# Heart-Earrings_2025-02-13.net
KiCad netlist of a schematic drawn in Altium Designer
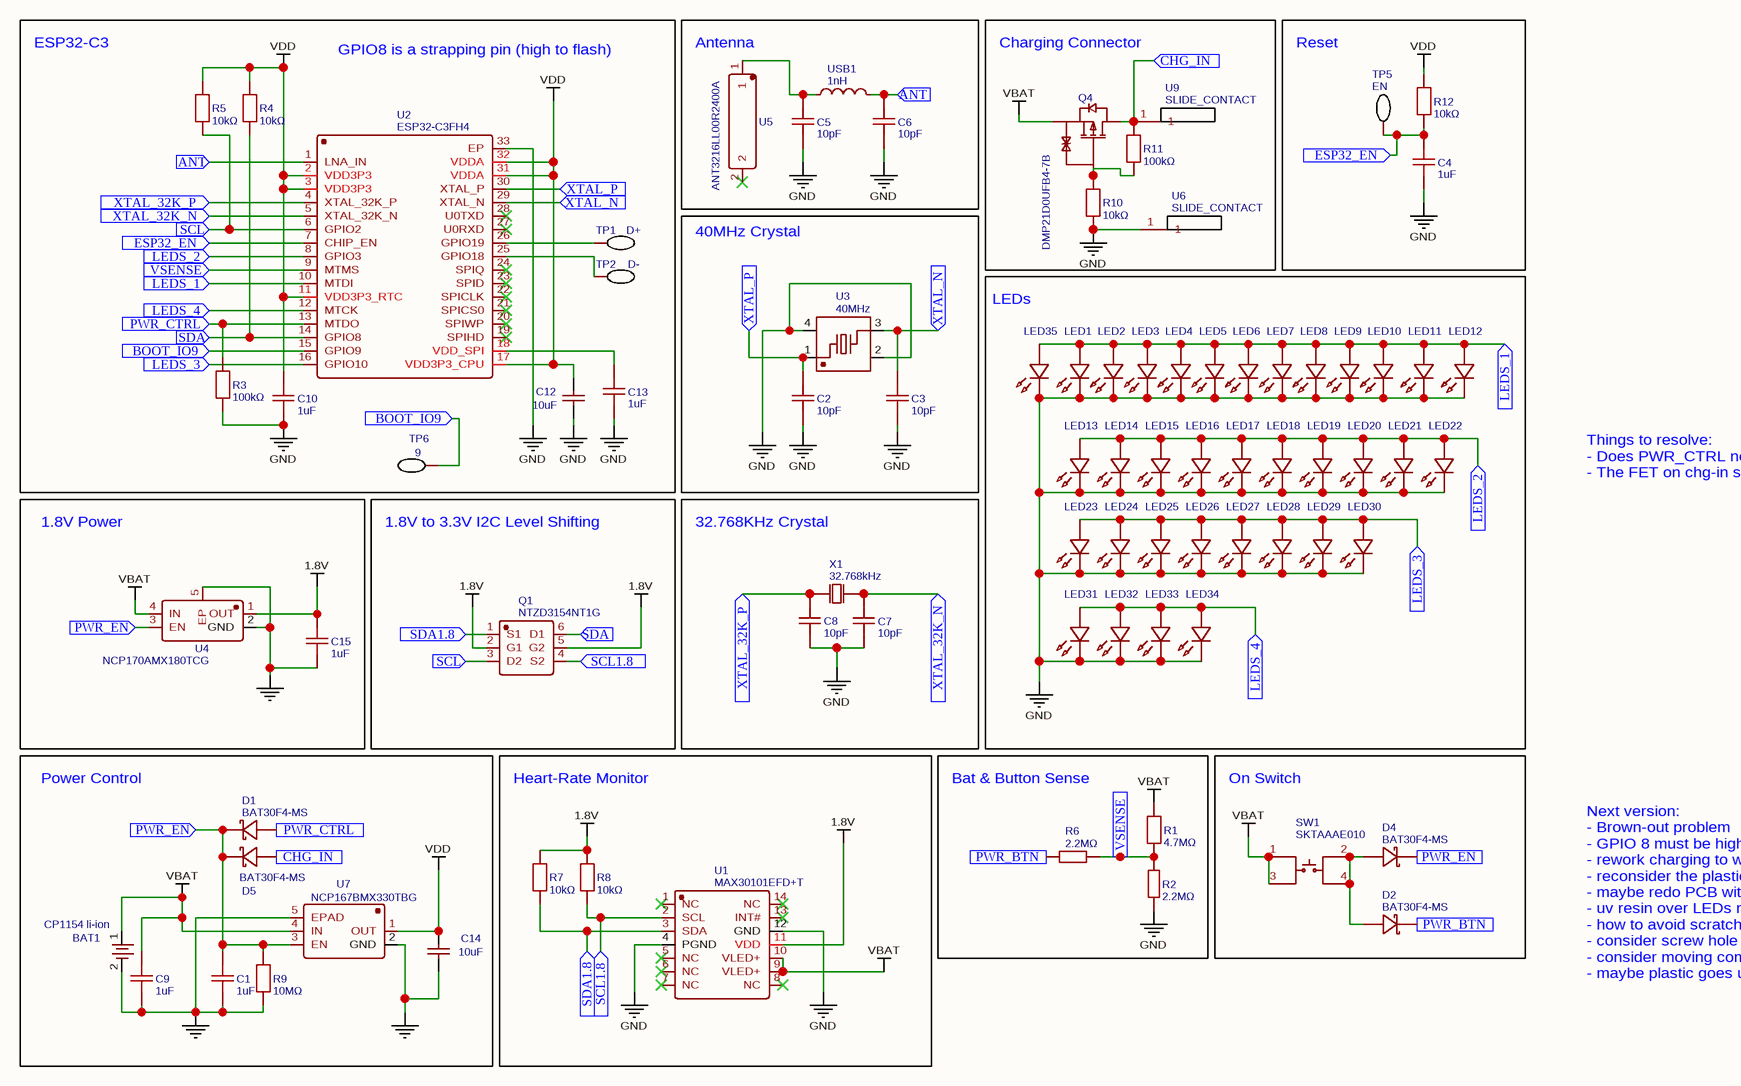
[diagram p0: Heart-Earrings_2025-02-13.schdoc]

(export (version "E")
  (design (tool "Eeschema 10.0.6"))
  (components
    (comp (ref "BAT1")
      (value "CP1154 li-ion")
      (fields
        (field (name "MANUFACTURER") "Varta")
        (field (name "MANUFACTURER PART") "MY-2032-10")
        (field (name "CONTRIBUTOR") "robdobsn")
      )
      (libsource (lib "altium-import") (part "root_3_CP1154 li-ion_"))
    )
    (comp (ref "C1")
      (value "1uF")
      (fields
        (field (name "MANUFACTURER") "SAMSUNG(三星)")
        (field (name "MANUFACTURER PART") "CL03A105MP3NSNH")
        (field (name "CONTRIBUTOR") "lcsc")
      )
      (libsource (lib "altium-import") (part "root_1_1uF_"))
    )
    (comp (ref "C2")
      (value "10pF")
      (fields
        (field (name "MANUFACTURER") "muRata(村田)")
        (field (name "MANUFACTURER PART") "GRM0335C1H100FA01D")
        (field (name "CONTRIBUTOR") "LCSC")
      )
      (libsource (lib "altium-import") (part "root_1_10pF_"))
    )
    (comp (ref "C3")
      (value "10pF")
      (fields
        (field (name "MANUFACTURER") "muRata(村田)")
        (field (name "MANUFACTURER PART") "GRM0335C1H100FA01D")
        (field (name "CONTRIBUTOR") "LCSC")
      )
      (libsource (lib "altium-import") (part "root_1_10pF_"))
    )
    (comp (ref "C4")
      (value "1uF")
      (fields
        (field (name "MANUFACTURER") "SAMSUNG(三星)")
        (field (name "MANUFACTURER PART") "CL03A105MP3NSNH")
        (field (name "CONTRIBUTOR") "lcsc")
      )
      (libsource (lib "altium-import") (part "root_1_1uF_"))
    )
    (comp (ref "C5")
      (value "10pF")
      (fields
        (field (name "MANUFACTURER") "muRata(村田)")
        (field (name "MANUFACTURER PART") "GRM0335C1H100FA01D")
        (field (name "CONTRIBUTOR") "LCSC")
      )
      (libsource (lib "altium-import") (part "root_1_10pF_"))
    )
    (comp (ref "C6")
      (value "10pF")
      (fields
        (field (name "MANUFACTURER") "muRata(村田)")
        (field (name "MANUFACTURER PART") "GRM0335C1H100FA01D")
        (field (name "CONTRIBUTOR") "LCSC")
      )
      (libsource (lib "altium-import") (part "root_1_10pF_"))
    )
    (comp (ref "C7")
      (value "10pF")
      (fields
        (field (name "MANUFACTURER") "muRata(村田)")
        (field (name "MANUFACTURER PART") "GRM0335C1H100FA01D")
        (field (name "CONTRIBUTOR") "LCSC")
      )
      (libsource (lib "altium-import") (part "root_1_10pF_"))
    )
    (comp (ref "C8")
      (value "10pF")
      (fields
        (field (name "MANUFACTURER") "muRata(村田)")
        (field (name "MANUFACTURER PART") "GRM0335C1H100FA01D")
        (field (name "CONTRIBUTOR") "LCSC")
      )
      (libsource (lib "altium-import") (part "root_3_10pF_"))
    )
    (comp (ref "C9")
      (value "1uF")
      (fields
        (field (name "MANUFACTURER") "SAMSUNG(三星)")
        (field (name "MANUFACTURER PART") "CL03A105MP3NSNH")
        (field (name "CONTRIBUTOR") "lcsc")
      )
      (libsource (lib "altium-import") (part "root_1_1uF_"))
    )
    (comp (ref "C10")
      (value "1uF")
      (fields
        (field (name "MANUFACTURER") "SAMSUNG(三星)")
        (field (name "MANUFACTURER PART") "CL03A105MP3NSNH")
        (field (name "CONTRIBUTOR") "lcsc")
      )
      (libsource (lib "altium-import") (part "root_1_1uF_"))
    )
    (comp (ref "C12")
      (value "10uF")
      (fields
        (field (name "MANUFACTURER PART") "CL05A106MQ5NUNC")
        (field (name "MANUFACTURER") "SAMSUNG(三星)")
      )
      (libsource (lib "altium-import") (part "root_1_10uF_"))
    )
    (comp (ref "C13")
      (value "1uF")
      (fields
        (field (name "MANUFACTURER") "SAMSUNG(三星)")
        (field (name "MANUFACTURER PART") "CL03A105MP3NSNH")
        (field (name "CONTRIBUTOR") "lcsc")
      )
      (libsource (lib "altium-import") (part "root_1_1uF_"))
    )
    (comp (ref "C14")
      (value "10uF")
      (fields
        (field (name "MANUFACTURER PART") "CL05A106MQ5NUNC")
        (field (name "MANUFACTURER") "SAMSUNG(三星)")
      )
      (libsource (lib "altium-import") (part "root_1_10uF_"))
    )
    (comp (ref "C15")
      (value "1uF")
      (fields
        (field (name "MANUFACTURER") "SAMSUNG(三星)")
        (field (name "MANUFACTURER PART") "CL03A105MP3NSNH")
        (field (name "CONTRIBUTOR") "lcsc")
      )
      (libsource (lib "altium-import") (part "root_1_1uF_"))
    )
    (comp (ref "D1")
      (value "BAT30F4-MS")
      (fields (field (name "MANUFACTURER") "MSKSEMI(美森科)") (field (name "CONTRIBUTOR") "lcsc"))
      (libsource (lib "altium-import") (part "root_0_BAT30F4-MS_"))
    )
    (comp (ref "D2")
      (value "BAT30F4-MS")
      (fields (field (name "MANUFACTURER") "MSKSEMI(美森科)") (field (name "CONTRIBUTOR") "lcsc"))
      (libsource (lib "altium-import") (part "root_2_BAT30F4-MS_"))
    )
    (comp (ref "D4")
      (value "BAT30F4-MS")
      (fields (field (name "MANUFACTURER") "MSKSEMI(美森科)") (field (name "CONTRIBUTOR") "lcsc"))
      (libsource (lib "altium-import") (part "root_2_BAT30F4-MS_"))
    )
    (comp (ref "D5")
      (value "BAT30F4-MS")
      (fields (field (name "MANUFACTURER") "MSKSEMI(美森科)") (field (name "CONTRIBUTOR") "lcsc"))
      (libsource (lib "altium-import") (part "root_0_BAT30F4-MS_"))
    )
    (comp (ref "LED1")
      (value "XL-0201SURC")
      (fields (field (name "MANUFACTURER") "XINGLIGHT(成兴光)") (field (name "CONTRIBUTOR") "lcsc"))
      (libsource (lib "altium-import") (part "root_1_XL-0201SURC_"))
    )
    (comp (ref "LED2")
      (value "XL-0201SURC")
      (fields (field (name "MANUFACTURER") "XINGLIGHT(成兴光)") (field (name "CONTRIBUTOR") "lcsc"))
      (libsource (lib "altium-import") (part "root_1_XL-0201SURC_"))
    )
    (comp (ref "LED3")
      (value "XL-0201SURC")
      (fields (field (name "MANUFACTURER") "XINGLIGHT(成兴光)") (field (name "CONTRIBUTOR") "lcsc"))
      (libsource (lib "altium-import") (part "root_1_XL-0201SURC_"))
    )
    (comp (ref "LED4")
      (value "XL-0201SURC")
      (fields (field (name "MANUFACTURER") "XINGLIGHT(成兴光)") (field (name "CONTRIBUTOR") "lcsc"))
      (libsource (lib "altium-import") (part "root_1_XL-0201SURC_"))
    )
    (comp (ref "LED5")
      (value "XL-0201SURC")
      (fields (field (name "MANUFACTURER") "XINGLIGHT(成兴光)") (field (name "CONTRIBUTOR") "lcsc"))
      (libsource (lib "altium-import") (part "root_1_XL-0201SURC_"))
    )
    (comp (ref "LED6")
      (value "XL-0201SURC")
      (fields (field (name "MANUFACTURER") "XINGLIGHT(成兴光)") (field (name "CONTRIBUTOR") "lcsc"))
      (libsource (lib "altium-import") (part "root_1_XL-0201SURC_"))
    )
    (comp (ref "LED7")
      (value "XL-0201SURC")
      (fields (field (name "MANUFACTURER") "XINGLIGHT(成兴光)") (field (name "CONTRIBUTOR") "lcsc"))
      (libsource (lib "altium-import") (part "root_1_XL-0201SURC_"))
    )
    (comp (ref "LED8")
      (value "XL-0201SURC")
      (fields (field (name "MANUFACTURER") "XINGLIGHT(成兴光)") (field (name "CONTRIBUTOR") "lcsc"))
      (libsource (lib "altium-import") (part "root_1_XL-0201SURC_"))
    )
    (comp (ref "LED9")
      (value "XL-0201SURC")
      (fields (field (name "MANUFACTURER") "XINGLIGHT(成兴光)") (field (name "CONTRIBUTOR") "lcsc"))
      (libsource (lib "altium-import") (part "root_1_XL-0201SURC_"))
    )
    (comp (ref "LED10")
      (value "XL-0201SURC")
      (fields (field (name "MANUFACTURER") "XINGLIGHT(成兴光)") (field (name "CONTRIBUTOR") "lcsc"))
      (libsource (lib "altium-import") (part "root_1_XL-0201SURC_"))
    )
    (comp (ref "LED11")
      (value "XL-0201SURC")
      (fields (field (name "MANUFACTURER") "XINGLIGHT(成兴光)") (field (name "CONTRIBUTOR") "lcsc"))
      (libsource (lib "altium-import") (part "root_1_XL-0201SURC_"))
    )
    (comp (ref "LED12")
      (value "XL-0201SURC")
      (fields (field (name "MANUFACTURER") "XINGLIGHT(成兴光)") (field (name "CONTRIBUTOR") "lcsc"))
      (libsource (lib "altium-import") (part "root_1_XL-0201SURC_"))
    )
    (comp (ref "LED13")
      (value "XL-0201SURC")
      (fields (field (name "MANUFACTURER") "XINGLIGHT(成兴光)") (field (name "CONTRIBUTOR") "lcsc"))
      (libsource (lib "altium-import") (part "root_1_XL-0201SURC_"))
    )
    (comp (ref "LED14")
      (value "XL-0201SURC")
      (fields (field (name "MANUFACTURER") "XINGLIGHT(成兴光)") (field (name "CONTRIBUTOR") "lcsc"))
      (libsource (lib "altium-import") (part "root_1_XL-0201SURC_"))
    )
    (comp (ref "LED15")
      (value "XL-0201SURC")
      (fields (field (name "MANUFACTURER") "XINGLIGHT(成兴光)") (field (name "CONTRIBUTOR") "lcsc"))
      (libsource (lib "altium-import") (part "root_1_XL-0201SURC_"))
    )
    (comp (ref "LED16")
      (value "XL-0201SURC")
      (fields (field (name "MANUFACTURER") "XINGLIGHT(成兴光)") (field (name "CONTRIBUTOR") "lcsc"))
      (libsource (lib "altium-import") (part "root_1_XL-0201SURC_"))
    )
    (comp (ref "LED17")
      (value "XL-0201SURC")
      (fields (field (name "MANUFACTURER") "XINGLIGHT(成兴光)") (field (name "CONTRIBUTOR") "lcsc"))
      (libsource (lib "altium-import") (part "root_1_XL-0201SURC_"))
    )
    (comp (ref "LED18")
      (value "XL-0201SURC")
      (fields (field (name "MANUFACTURER") "XINGLIGHT(成兴光)") (field (name "CONTRIBUTOR") "lcsc"))
      (libsource (lib "altium-import") (part "root_1_XL-0201SURC_"))
    )
    (comp (ref "LED19")
      (value "XL-0201SURC")
      (fields (field (name "MANUFACTURER") "XINGLIGHT(成兴光)") (field (name "CONTRIBUTOR") "lcsc"))
      (libsource (lib "altium-import") (part "root_1_XL-0201SURC_"))
    )
    (comp (ref "LED20")
      (value "XL-0201SURC")
      (fields (field (name "MANUFACTURER") "XINGLIGHT(成兴光)") (field (name "CONTRIBUTOR") "lcsc"))
      (libsource (lib "altium-import") (part "root_1_XL-0201SURC_"))
    )
    (comp (ref "LED21")
      (value "XL-0201SURC")
      (fields (field (name "MANUFACTURER") "XINGLIGHT(成兴光)") (field (name "CONTRIBUTOR") "lcsc"))
      (libsource (lib "altium-import") (part "root_1_XL-0201SURC_"))
    )
    (comp (ref "LED22")
      (value "XL-0201SURC")
      (fields (field (name "MANUFACTURER") "XINGLIGHT(成兴光)") (field (name "CONTRIBUTOR") "lcsc"))
      (libsource (lib "altium-import") (part "root_1_XL-0201SURC_"))
    )
    (comp (ref "LED23")
      (value "XL-0201SURC")
      (fields (field (name "MANUFACTURER") "XINGLIGHT(成兴光)") (field (name "CONTRIBUTOR") "lcsc"))
      (libsource (lib "altium-import") (part "root_1_XL-0201SURC_"))
    )
    (comp (ref "LED24")
      (value "XL-0201SURC")
      (fields (field (name "MANUFACTURER") "XINGLIGHT(成兴光)") (field (name "CONTRIBUTOR") "lcsc"))
      (libsource (lib "altium-import") (part "root_1_XL-0201SURC_"))
    )
    (comp (ref "LED25")
      (value "XL-0201SURC")
      (fields (field (name "MANUFACTURER") "XINGLIGHT(成兴光)") (field (name "CONTRIBUTOR") "lcsc"))
      (libsource (lib "altium-import") (part "root_1_XL-0201SURC_"))
    )
    (comp (ref "LED26")
      (value "XL-0201SURC")
      (fields (field (name "MANUFACTURER") "XINGLIGHT(成兴光)") (field (name "CONTRIBUTOR") "lcsc"))
      (libsource (lib "altium-import") (part "root_1_XL-0201SURC_"))
    )
    (comp (ref "LED27")
      (value "XL-0201SURC")
      (fields (field (name "MANUFACTURER") "XINGLIGHT(成兴光)") (field (name "CONTRIBUTOR") "lcsc"))
      (libsource (lib "altium-import") (part "root_1_XL-0201SURC_"))
    )
    (comp (ref "LED28")
      (value "XL-0201SURC")
      (fields (field (name "MANUFACTURER") "XINGLIGHT(成兴光)") (field (name "CONTRIBUTOR") "lcsc"))
      (libsource (lib "altium-import") (part "root_1_XL-0201SURC_"))
    )
    (comp (ref "LED29")
      (value "XL-0201SURC")
      (fields (field (name "MANUFACTURER") "XINGLIGHT(成兴光)") (field (name "CONTRIBUTOR") "lcsc"))
      (libsource (lib "altium-import") (part "root_1_XL-0201SURC_"))
    )
    (comp (ref "LED30")
      (value "XL-0201SURC")
      (fields (field (name "MANUFACTURER") "XINGLIGHT(成兴光)") (field (name "CONTRIBUTOR") "lcsc"))
      (libsource (lib "altium-import") (part "root_1_XL-0201SURC_"))
    )
    (comp (ref "LED31")
      (value "XL-0201SURC")
      (fields (field (name "MANUFACTURER") "XINGLIGHT(成兴光)") (field (name "CONTRIBUTOR") "lcsc"))
      (libsource (lib "altium-import") (part "root_1_XL-0201SURC_"))
    )
    (comp (ref "LED32")
      (value "XL-0201SURC")
      (fields (field (name "MANUFACTURER") "XINGLIGHT(成兴光)") (field (name "CONTRIBUTOR") "lcsc"))
      (libsource (lib "altium-import") (part "root_1_XL-0201SURC_"))
    )
    (comp (ref "LED33")
      (value "XL-0201SURC")
      (fields (field (name "MANUFACTURER") "XINGLIGHT(成兴光)") (field (name "CONTRIBUTOR") "lcsc"))
      (libsource (lib "altium-import") (part "root_1_XL-0201SURC_"))
    )
    (comp (ref "LED34")
      (value "XL-0201SURC")
      (fields (field (name "MANUFACTURER") "XINGLIGHT(成兴光)") (field (name "CONTRIBUTOR") "lcsc"))
      (libsource (lib "altium-import") (part "root_1_XL-0201SURC_"))
    )
    (comp (ref "LED35")
      (value "XL-0201SURC")
      (fields (field (name "MANUFACTURER") "XINGLIGHT(成兴光)") (field (name "CONTRIBUTOR") "lcsc"))
      (libsource (lib "altium-import") (part "root_1_XL-0201SURC_"))
    )
    (comp (ref "Q1")
      (value "NTZD3154NT1G")
      (fields (field (name "MANUFACTURER") "onsemi(安森美)") (field (name "CONTRIBUTOR") "LCSC"))
      (libsource (lib "altium-import") (part "root_0_NTZD3154NT1G_"))
    )
    (comp (ref "Q4")
      (value "DMP21D0UFB4-7B")
      (fields (field (name "MANUFACTURER") "DIODES(美台)") (field (name "CONTRIBUTOR") "LCSC"))
      (libsource (lib "altium-import") (part "root_3_DMP21D0UFB4-7B_"))
    )
    (comp (ref "R1")
      (value "4.7MΩ")
      (fields
        (field (name "MANUFACTURER") "UNI-ROYAL(厚声)")
        (field (name "MANUFACTURER PART") "0201WMF4704TEE")
        (field (name "CONTRIBUTOR") "LCSC")
      )
      (libsource (lib "altium-import") (part "root_1_4.7MΩ_"))
    )
    (comp (ref "R2")
      (value "2.2MΩ")
      (fields
        (field (name "MANUFACTURER") "YAGEO(国巨)")
        (field (name "MANUFACTURER PART") "RC0201FR-072M2L")
        (field (name "CONTRIBUTOR") "lcsc")
      )
      (libsource (lib "altium-import") (part "root_1_2.2MΩ_"))
    )
    (comp (ref "R3")
      (value "100kΩ")
      (fields
        (field (name "MANUFACTURER") "VISHAY(威世)")
        (field (name "MANUFACTURER PART") "CRCW0201100KFKED")
        (field (name "CONTRIBUTOR") "lcsc")
      )
      (libsource (lib "altium-import") (part "root_1_100kΩ_"))
    )
    (comp (ref "R4")
      (value "10kΩ")
      (fields
        (field (name "MANUFACTURER") "VISHAY(威世)")
        (field (name "MANUFACTURER PART") "CRCW020110K0FKED")
        (field (name "CONTRIBUTOR") "LCSC")
      )
      (libsource (lib "altium-import") (part "root_1_10kΩ_"))
    )
    (comp (ref "R5")
      (value "10kΩ")
      (fields
        (field (name "MANUFACTURER") "VISHAY(威世)")
        (field (name "MANUFACTURER PART") "CRCW020110K0FKED")
        (field (name "CONTRIBUTOR") "LCSC")
      )
      (libsource (lib "altium-import") (part "root_1_10kΩ_"))
    )
    (comp (ref "R6")
      (value "2.2MΩ")
      (fields
        (field (name "MANUFACTURER") "YAGEO(国巨)")
        (field (name "MANUFACTURER PART") "RC0201FR-072M2L")
        (field (name "CONTRIBUTOR") "lcsc")
      )
      (libsource (lib "altium-import") (part "root_2_2.2MΩ_"))
    )
    (comp (ref "R7")
      (value "10kΩ")
      (fields
        (field (name "MANUFACTURER") "VISHAY(威世)")
        (field (name "MANUFACTURER PART") "CRCW020110K0FKED")
        (field (name "CONTRIBUTOR") "LCSC")
      )
      (libsource (lib "altium-import") (part "root_1_10kΩ_"))
    )
    (comp (ref "R8")
      (value "10kΩ")
      (fields
        (field (name "MANUFACTURER") "VISHAY(威世)")
        (field (name "MANUFACTURER PART") "CRCW020110K0FKED")
        (field (name "CONTRIBUTOR") "LCSC")
      )
      (libsource (lib "altium-import") (part "root_1_10kΩ_"))
    )
    (comp (ref "R9")
      (value "10MΩ")
      (fields
        (field (name "MANUFACTURER") "UNI-ROYAL(厚声)")
        (field (name "MANUFACTURER PART") "0201WMF1005TEE")
        (field (name "CONTRIBUTOR") "lcsc")
      )
      (libsource (lib "altium-import") (part "root_1_10MΩ_"))
    )
    (comp (ref "R10")
      (value "10kΩ")
      (fields
        (field (name "MANUFACTURER") "VISHAY(威世)")
        (field (name "MANUFACTURER PART") "CRCW020110K0FKED")
        (field (name "CONTRIBUTOR") "LCSC")
      )
      (libsource (lib "altium-import") (part "root_1_10kΩ_"))
    )
    (comp (ref "R11")
      (value "100kΩ")
      (fields
        (field (name "MANUFACTURER") "VISHAY(威世)")
        (field (name "MANUFACTURER PART") "CRCW0201100KFKED")
        (field (name "CONTRIBUTOR") "lcsc")
      )
      (libsource (lib "altium-import") (part "root_1_100kΩ_"))
    )
    (comp (ref "R12")
      (value "10kΩ")
      (fields
        (field (name "MANUFACTURER") "VISHAY(威世)")
        (field (name "MANUFACTURER PART") "CRCW020110K0FKED")
        (field (name "CONTRIBUTOR") "LCSC")
      )
      (libsource (lib "altium-import") (part "root_1_10kΩ_"))
    )
    (comp (ref "SW1")
      (value "SKTAAAE010")
      (fields (field (name "MANUFACTURER") "ALPSALPINE(阿尔卑斯阿尔派)") (field (name "CONTRIBUTOR") "LCSC"))
      (libsource (lib "altium-import") (part "root_0_SKTAAAE010_"))
    )
    (comp (ref "TP1")
      (value "D+")
      (fields (field (name "MANUFACTURER PART") "TESTPAD") (field (name "CONTRIBUTOR") "wenjuntijee"))
      (libsource (lib "altium-import") (part "root_2_D+_"))
    )
    (comp (ref "TP2")
      (value "D-")
      (fields (field (name "MANUFACTURER PART") "TESTPAD") (field (name "CONTRIBUTOR") "wenjuntijee"))
      (libsource (lib "altium-import") (part "root_2_D-_"))
    )
    (comp (ref "TP5")
      (value "EN")
      (fields (field (name "MANUFACTURER PART") "TESTPAD") (field (name "CONTRIBUTOR") "wenjuntijee"))
      (libsource (lib "altium-import") (part "root_3_EN_"))
    )
    (comp (ref "TP6")
      (value "9")
      (fields (field (name "MANUFACTURER PART") "TESTPAD") (field (name "CONTRIBUTOR") "wenjuntijee"))
      (libsource (lib "altium-import") (part "root_0_9_"))
    )
    (comp (ref "U1")
      (value "MAX30101EFD+T")
      (fields (field (name "MANUFACTURER") "MAXIM(美信)") (field (name "CONTRIBUTOR") "LCSC"))
      (libsource (lib "altium-import") (part "root_0_MAX30101EFD+T_"))
    )
    (comp (ref "U2")
      (value "ESP32-C3FH4")
      (fields (field (name "MANUFACTURER") "ESPRESSIF(乐鑫)") (field (name "CONTRIBUTOR") "LCSC"))
      (libsource (lib "altium-import") (part "root_0_ESP32-C3FH4_"))
    )
    (comp (ref "U3")
      (value "40MHz")
      (fields
        (field (name "MANUFACTURER") "JYJE(晶友嘉)")
        (field (name "MANUFACTURER PART") "TJ1140000HYGBC")
        (field (name "CONTRIBUTOR") "lcsc")
      )
      (libsource (lib "altium-import") (part "root_0_40MHz_"))
    )
    (comp (ref "U4")
      (value "NCP170AMX180TCG")
      (fields (field (name "MANUFACTURER") "onsemi(安森美)") (field (name "CONTRIBUTOR") "LCSC"))
      (libsource (lib "altium-import") (part "root_0_NCP170AMX180TCG_"))
    )
    (comp (ref "U5")
      (value "ANT3216LL00R2400A")
      (fields (field (name "MANUFACTURER") "YAGEO(国巨)") (field (name "CONTRIBUTOR") "LCSC"))
      (libsource (lib "altium-import") (part "root_3_ANT3216LL00R2400A_"))
    )
    (comp (ref "U6")
      (value "SLIDE_CONTACT")
      (fields (field (name "CONTRIBUTOR") "robdobsn"))
      (libsource (lib "altium-import") (part "root_2_SLIDE_CONTACT_"))
    )
    (comp (ref "U7")
      (value "NCP167BMX330TBG")
      (fields (field (name "MANUFACTURER") "onsemi(安森美)") (field (name "CONTRIBUTOR") "LCSC"))
      (libsource (lib "altium-import") (part "root_0_NCP167BMX330TBG_"))
    )
    (comp (ref "U9")
      (value "SLIDE_CONTACT")
      (fields (field (name "CONTRIBUTOR") "robdobsn"))
      (libsource (lib "altium-import") (part "root_2_SLIDE_CONTACT_"))
    )
    (comp (ref "USB1")
      (value "1nH")
      (fields
        (field (name "MANUFACTURER") "TDK")
        (field (name "MANUFACTURER PART") "MLG0603P1N0BTD25")
        (field (name "CONTRIBUTOR") "LCSC")
      )
      (libsource (lib "altium-import") (part "root_0_1nH_"))
    )
    (comp (ref "X1")
      (value "32.768kHz")
      (fields
        (field (name "MANUFACTURER") "EPSON(爱普生)")
        (field (name "MANUFACTURER PART") "X1A000121000500")
        (field (name "CONTRIBUTOR") "lcsc")
      )
      (libsource (lib "altium-import") (part "root_2_32.768kHz_"))
    )
  )
  (nets
    (net (code "1") (name "/ANT") (class "Default")
      (node (ref "C6") (pin "2") (pinfunction "2_2") (pintype "passive"))
      (node (ref "U2") (pin "1") (pinfunction "LNA_IN_1") (pintype "passive"))
      (node (ref "USB1") (pin "2") (pinfunction "2_2") (pintype "passive"))
    )
    (net (code "2") (name "/BOOT_IO9") (class "Default")
      (node (ref "TP6") (pin "1") (pinfunction "1_1") (pintype "passive"))
      (node (ref "U2") (pin "15") (pinfunction "GPIO9_15") (pintype "passive"))
    )
    (net (code "3") (name "/CHG_IN") (class "Default")
      (node (ref "D5") (pin "2") (pinfunction "A_2") (pintype "passive"))
      (node (ref "Q4") (pin "3") (pinfunction "D_3") (pintype "passive"))
      (node (ref "R11") (pin "2") (pinfunction "2_2") (pintype "passive"))
      (node (ref "U9") (pin "1") (pinfunction "1_1") (pintype "passive"))
    )
    (net (code "4") (name "/ESP32_EN") (class "Default")
      (node (ref "C4") (pin "2") (pinfunction "2_2") (pintype "passive"))
      (node (ref "R12") (pin "1") (pinfunction "1_1") (pintype "passive"))
      (node (ref "TP5") (pin "1") (pinfunction "1_1") (pintype "passive"))
      (node (ref "U2") (pin "7") (pinfunction "CHIP_EN_7") (pintype "passive"))
    )
    (net (code "5") (name "/LEDS_1") (class "Default")
      (node (ref "LED1") (pin "2") (pinfunction "A_2") (pintype "passive"))
      (node (ref "LED10") (pin "2") (pinfunction "A_2") (pintype "passive"))
      (node (ref "LED11") (pin "2") (pinfunction "A_2") (pintype "passive"))
      (node (ref "LED12") (pin "2") (pinfunction "A_2") (pintype "passive"))
      (node (ref "LED2") (pin "2") (pinfunction "A_2") (pintype "passive"))
      (node (ref "LED3") (pin "2") (pinfunction "A_2") (pintype "passive"))
      (node (ref "LED35") (pin "2") (pinfunction "A_2") (pintype "passive"))
      (node (ref "LED4") (pin "2") (pinfunction "A_2") (pintype "passive"))
      (node (ref "LED5") (pin "2") (pinfunction "A_2") (pintype "passive"))
      (node (ref "LED6") (pin "2") (pinfunction "A_2") (pintype "passive"))
      (node (ref "LED7") (pin "2") (pinfunction "A_2") (pintype "passive"))
      (node (ref "LED8") (pin "2") (pinfunction "A_2") (pintype "passive"))
      (node (ref "LED9") (pin "2") (pinfunction "A_2") (pintype "passive"))
      (node (ref "U2") (pin "10") (pinfunction "MTDI_10") (pintype "passive"))
    )
    (net (code "6") (name "/LEDS_2") (class "Default")
      (node (ref "LED13") (pin "2") (pinfunction "A_2") (pintype "passive"))
      (node (ref "LED14") (pin "2") (pinfunction "A_2") (pintype "passive"))
      (node (ref "LED15") (pin "2") (pinfunction "A_2") (pintype "passive"))
      (node (ref "LED16") (pin "2") (pinfunction "A_2") (pintype "passive"))
      (node (ref "LED17") (pin "2") (pinfunction "A_2") (pintype "passive"))
      (node (ref "LED18") (pin "2") (pinfunction "A_2") (pintype "passive"))
      (node (ref "LED19") (pin "2") (pinfunction "A_2") (pintype "passive"))
      (node (ref "LED20") (pin "2") (pinfunction "A_2") (pintype "passive"))
      (node (ref "LED21") (pin "2") (pinfunction "A_2") (pintype "passive"))
      (node (ref "LED22") (pin "2") (pinfunction "A_2") (pintype "passive"))
      (node (ref "U2") (pin "8") (pinfunction "GPIO3_8") (pintype "passive"))
    )
    (net (code "7") (name "/LEDS_3") (class "Default")
      (node (ref "LED23") (pin "2") (pinfunction "A_2") (pintype "passive"))
      (node (ref "LED24") (pin "2") (pinfunction "A_2") (pintype "passive"))
      (node (ref "LED25") (pin "2") (pinfunction "A_2") (pintype "passive"))
      (node (ref "LED26") (pin "2") (pinfunction "A_2") (pintype "passive"))
      (node (ref "LED27") (pin "2") (pinfunction "A_2") (pintype "passive"))
      (node (ref "LED28") (pin "2") (pinfunction "A_2") (pintype "passive"))
      (node (ref "LED29") (pin "2") (pinfunction "A_2") (pintype "passive"))
      (node (ref "LED30") (pin "2") (pinfunction "A_2") (pintype "passive"))
      (node (ref "U2") (pin "16") (pinfunction "GPIO10_16") (pintype "passive"))
    )
    (net (code "8") (name "/LEDS_4") (class "Default")
      (node (ref "LED31") (pin "2") (pinfunction "A_2") (pintype "passive"))
      (node (ref "LED32") (pin "2") (pinfunction "A_2") (pintype "passive"))
      (node (ref "LED33") (pin "2") (pinfunction "A_2") (pintype "passive"))
      (node (ref "LED34") (pin "2") (pinfunction "A_2") (pintype "passive"))
      (node (ref "U2") (pin "12") (pinfunction "MTCK_12") (pintype "passive"))
    )
    (net (code "9") (name "/PWR_BTN") (class "Default")
      (node (ref "D2") (pin "1") (pinfunction "K_1") (pintype "passive"))
      (node (ref "R6") (pin "2") (pinfunction "2_2") (pintype "passive"))
    )
    (net (code "10") (name "/PWR_CTRL") (class "Default")
      (node (ref "D1") (pin "2") (pinfunction "A_2") (pintype "passive"))
      (node (ref "R3") (pin "2") (pinfunction "2_2") (pintype "passive"))
      (node (ref "U2") (pin "13") (pinfunction "MTDO_13") (pintype "passive"))
    )
    (net (code "11") (name "/PWR_EN") (class "Default")
      (node (ref "C1") (pin "2") (pinfunction "2_2") (pintype "passive"))
      (node (ref "D1") (pin "1") (pinfunction "K_1") (pintype "passive"))
      (node (ref "D4") (pin "1") (pinfunction "K_1") (pintype "passive"))
      (node (ref "D5") (pin "1") (pinfunction "K_1") (pintype "passive"))
      (node (ref "R9") (pin "2") (pinfunction "2_2") (pintype "passive"))
      (node (ref "U4") (pin "3") (pinfunction "EN_3") (pintype "passive"))
      (node (ref "U7") (pin "3") (pinfunction "EN_3") (pintype "passive"))
    )
    (net (code "12") (name "/SCL") (class "Default")
      (node (ref "Q1") (pin "3") (pinfunction "D2_3") (pintype "passive"))
      (node (ref "R5") (pin "1") (pinfunction "1_1") (pintype "passive"))
      (node (ref "U2") (pin "6") (pinfunction "GPIO2_6") (pintype "passive"))
    )
    (net (code "13") (name "/SCL1.8") (class "Default")
      (node (ref "Q1") (pin "4") (pinfunction "S2_4") (pintype "passive"))
      (node (ref "R8") (pin "1") (pinfunction "1_1") (pintype "passive"))
      (node (ref "U1") (pin "2") (pinfunction "SCL_2") (pintype "passive"))
    )
    (net (code "14") (name "/SDA") (class "Default")
      (node (ref "Q1") (pin "6") (pinfunction "D1_6") (pintype "passive"))
      (node (ref "R4") (pin "1") (pinfunction "1_1") (pintype "passive"))
      (node (ref "U2") (pin "14") (pinfunction "GPIO8_14") (pintype "passive"))
    )
    (net (code "15") (name "/SDA1.8") (class "Default")
      (node (ref "Q1") (pin "1") (pinfunction "S1_1") (pintype "passive"))
      (node (ref "R7") (pin "1") (pinfunction "1_1") (pintype "passive"))
      (node (ref "U1") (pin "3") (pinfunction "SDA_3") (pintype "passive"))
    )
    (net (code "16") (name "/VSENSE") (class "Default")
      (node (ref "R1") (pin "1") (pinfunction "1_1") (pintype "passive"))
      (node (ref "R2") (pin "2") (pinfunction "2_2") (pintype "passive"))
      (node (ref "R6") (pin "1") (pinfunction "1_1") (pintype "passive"))
      (node (ref "U2") (pin "9") (pinfunction "MTMS_9") (pintype "passive"))
    )
    (net (code "17") (name "/XTAL_32K_N") (class "Default")
      (node (ref "C7") (pin "2") (pinfunction "2_2") (pintype "passive"))
      (node (ref "U2") (pin "5") (pinfunction "XTAL_32K_N_5") (pintype "passive"))
      (node (ref "X1") (pin "1") (pinfunction "OSC1_1") (pintype "passive"))
    )
    (net (code "18") (name "/XTAL_32K_P") (class "Default")
      (node (ref "C8") (pin "1") (pinfunction "1_1") (pintype "passive"))
      (node (ref "U2") (pin "4") (pinfunction "XTAL_32K_P_4") (pintype "passive"))
      (node (ref "X1") (pin "2") (pinfunction "OSC2_2") (pintype "passive"))
    )
    (net (code "19") (name "/XTAL_N") (class "Default")
      (node (ref "C3") (pin "2") (pinfunction "2_2") (pintype "passive"))
      (node (ref "U2") (pin "29") (pinfunction "XTAL_N_29") (pintype "passive"))
      (node (ref "U3") (pin "3") (pinfunction "3_3") (pintype "passive"))
    )
    (net (code "20") (name "/XTAL_P") (class "Default")
      (node (ref "C2") (pin "2") (pinfunction "2_2") (pintype "passive"))
      (node (ref "U2") (pin "30") (pinfunction "XTAL_P_30") (pintype "passive"))
      (node (ref "U3") (pin "1") (pinfunction "1_1") (pintype "passive"))
    )
    (net (code "21") (name "1.8V") (class "Default")
      (node (ref "C15") (pin "2") (pinfunction "2_2") (pintype "passive"))
      (node (ref "Q1") (pin "2") (pinfunction "G1_2") (pintype "passive"))
      (node (ref "Q1") (pin "5") (pinfunction "G2_5") (pintype "passive"))
      (node (ref "R7") (pin "2") (pinfunction "2_2") (pintype "passive"))
      (node (ref "R8") (pin "2") (pinfunction "2_2") (pintype "passive"))
      (node (ref "U1") (pin "11") (pinfunction "VDD_11") (pintype "passive"))
      (node (ref "U4") (pin "1") (pinfunction "OUT_1") (pintype "passive"))
    )
    (net (code "22") (name "GND") (class "Default")
      (node (ref "BAT1") (pin "2") (pinfunction "BAT-_2") (pintype "passive"))
      (node (ref "C1") (pin "1") (pinfunction "1_1") (pintype "passive"))
      (node (ref "C10") (pin "1") (pinfunction "1_1") (pintype "passive"))
      (node (ref "C12") (pin "1") (pinfunction "1_1") (pintype "passive"))
      (node (ref "C13") (pin "1") (pinfunction "1_1") (pintype "passive"))
      (node (ref "C14") (pin "1") (pinfunction "1_1") (pintype "passive"))
      (node (ref "C15") (pin "1") (pinfunction "1_1") (pintype "passive"))
      (node (ref "C2") (pin "1") (pinfunction "1_1") (pintype "passive"))
      (node (ref "C3") (pin "1") (pinfunction "1_1") (pintype "passive"))
      (node (ref "C4") (pin "1") (pinfunction "1_1") (pintype "passive"))
      (node (ref "C5") (pin "1") (pinfunction "1_1") (pintype "passive"))
      (node (ref "C6") (pin "1") (pinfunction "1_1") (pintype "passive"))
      (node (ref "C7") (pin "1") (pinfunction "1_1") (pintype "passive"))
      (node (ref "C8") (pin "2") (pinfunction "2_2") (pintype "passive"))
      (node (ref "C9") (pin "1") (pinfunction "1_1") (pintype "passive"))
      (node (ref "LED1") (pin "1") (pinfunction "K_1") (pintype "passive"))
      (node (ref "LED10") (pin "1") (pinfunction "K_1") (pintype "passive"))
      (node (ref "LED11") (pin "1") (pinfunction "K_1") (pintype "passive"))
      (node (ref "LED12") (pin "1") (pinfunction "K_1") (pintype "passive"))
      (node (ref "LED13") (pin "1") (pinfunction "K_1") (pintype "passive"))
      (node (ref "LED14") (pin "1") (pinfunction "K_1") (pintype "passive"))
      (node (ref "LED15") (pin "1") (pinfunction "K_1") (pintype "passive"))
      (node (ref "LED16") (pin "1") (pinfunction "K_1") (pintype "passive"))
      (node (ref "LED17") (pin "1") (pinfunction "K_1") (pintype "passive"))
      (node (ref "LED18") (pin "1") (pinfunction "K_1") (pintype "passive"))
      (node (ref "LED19") (pin "1") (pinfunction "K_1") (pintype "passive"))
      (node (ref "LED2") (pin "1") (pinfunction "K_1") (pintype "passive"))
      (node (ref "LED20") (pin "1") (pinfunction "K_1") (pintype "passive"))
      (node (ref "LED21") (pin "1") (pinfunction "K_1") (pintype "passive"))
      (node (ref "LED22") (pin "1") (pinfunction "K_1") (pintype "passive"))
      (node (ref "LED23") (pin "1") (pinfunction "K_1") (pintype "passive"))
      (node (ref "LED24") (pin "1") (pinfunction "K_1") (pintype "passive"))
      (node (ref "LED25") (pin "1") (pinfunction "K_1") (pintype "passive"))
      (node (ref "LED26") (pin "1") (pinfunction "K_1") (pintype "passive"))
      (node (ref "LED27") (pin "1") (pinfunction "K_1") (pintype "passive"))
      (node (ref "LED28") (pin "1") (pinfunction "K_1") (pintype "passive"))
      (node (ref "LED29") (pin "1") (pinfunction "K_1") (pintype "passive"))
      (node (ref "LED3") (pin "1") (pinfunction "K_1") (pintype "passive"))
      (node (ref "LED30") (pin "1") (pinfunction "K_1") (pintype "passive"))
      (node (ref "LED31") (pin "1") (pinfunction "K_1") (pintype "passive"))
      (node (ref "LED32") (pin "1") (pinfunction "K_1") (pintype "passive"))
      (node (ref "LED33") (pin "1") (pinfunction "K_1") (pintype "passive"))
      (node (ref "LED34") (pin "1") (pinfunction "K_1") (pintype "passive"))
      (node (ref "LED35") (pin "1") (pinfunction "K_1") (pintype "passive"))
      (node (ref "LED4") (pin "1") (pinfunction "K_1") (pintype "passive"))
      (node (ref "LED5") (pin "1") (pinfunction "K_1") (pintype "passive"))
      (node (ref "LED6") (pin "1") (pinfunction "K_1") (pintype "passive"))
      (node (ref "LED7") (pin "1") (pinfunction "K_1") (pintype "passive"))
      (node (ref "LED8") (pin "1") (pinfunction "K_1") (pintype "passive"))
      (node (ref "LED9") (pin "1") (pinfunction "K_1") (pintype "passive"))
      (node (ref "R10") (pin "1") (pinfunction "1_1") (pintype "passive"))
      (node (ref "R2") (pin "1") (pinfunction "1_1") (pintype "passive"))
      (node (ref "R3") (pin "1") (pinfunction "1_1") (pintype "passive"))
      (node (ref "R9") (pin "1") (pinfunction "1_1") (pintype "passive"))
      (node (ref "U1") (pin "12") (pinfunction "GND_12") (pintype "passive"))
      (node (ref "U1") (pin "4") (pinfunction "PGND_4") (pintype "passive"))
      (node (ref "U2") (pin "33") (pinfunction "EP_33") (pintype "passive"))
      (node (ref "U3") (pin "2") (pinfunction "GND_2") (pintype "passive"))
      (node (ref "U3") (pin "4") (pinfunction "GND_4") (pintype "passive"))
      (node (ref "U4") (pin "2") (pinfunction "GND_2") (pintype "passive"))
      (node (ref "U4") (pin "5") (pinfunction "EP_5") (pintype "passive"))
      (node (ref "U6") (pin "1") (pinfunction "1_1") (pintype "passive"))
      (node (ref "U7") (pin "2") (pinfunction "GND_2") (pintype "passive"))
      (node (ref "U7") (pin "5") (pinfunction "EPAD_5") (pintype "passive"))
    )
    (net (code "23") (name "Net-(C5-Pad2)") (class "Default")
      (node (ref "C5") (pin "2") (pinfunction "2_2") (pintype "passive"))
      (node (ref "U5") (pin "1") (pinfunction "1_1") (pintype "passive"))
      (node (ref "USB1") (pin "1") (pinfunction "1_1") (pintype "passive"))
    )
    (net (code "24") (name "Net-(D2-A)") (class "Default")
      (node (ref "D2") (pin "2") (pinfunction "A_2") (pintype "passive"))
      (node (ref "D4") (pin "2") (pinfunction "A_2") (pintype "passive"))
      (node (ref "SW1") (pin "2") (pinfunction "2_2") (pintype "passive"))
      (node (ref "SW1") (pin "4") (pinfunction "4_4") (pintype "passive"))
    )
    (net (code "25") (name "Net-(Q4-G)") (class "Default")
      (node (ref "Q4") (pin "1") (pinfunction "G_1") (pintype "passive"))
      (node (ref "R10") (pin "2") (pinfunction "2_2") (pintype "passive"))
      (node (ref "R11") (pin "1") (pinfunction "1_1") (pintype "passive"))
    )
    (net (code "26") (name "Net-(U2-GPIO18)") (class "Default")
      (node (ref "TP2") (pin "1") (pinfunction "1_1") (pintype "passive"))
      (node (ref "U2") (pin "25") (pinfunction "GPIO18_25") (pintype "passive"))
    )
    (net (code "27") (name "Net-(U2-GPIO19)") (class "Default")
      (node (ref "TP1") (pin "1") (pinfunction "1_1") (pintype "passive"))
      (node (ref "U2") (pin "26") (pinfunction "GPIO19_26") (pintype "passive"))
    )
    (net (code "28") (name "Net-(U2-VDD_SPI)") (class "Default")
      (node (ref "C13") (pin "2") (pinfunction "2_2") (pintype "passive"))
      (node (ref "U2") (pin "18") (pinfunction "VDD_SPI_18") (pintype "passive"))
    )
    (net (code "29") (name "VBAT") (class "Default")
      (node (ref "BAT1") (pin "1") (pinfunction "BAT+_1") (pintype "passive"))
      (node (ref "C9") (pin "2") (pinfunction "2_2") (pintype "passive"))
      (node (ref "Q4") (pin "2") (pinfunction "S_2") (pintype "passive"))
      (node (ref "R1") (pin "2") (pinfunction "2_2") (pintype "passive"))
      (node (ref "SW1") (pin "1") (pinfunction "1_1") (pintype "passive"))
      (node (ref "SW1") (pin "3") (pinfunction "3_3") (pintype "passive"))
      (node (ref "U1") (pin "10") (pinfunction "VLED+_10") (pintype "passive"))
      (node (ref "U1") (pin "9") (pinfunction "VLED+_9") (pintype "passive"))
      (node (ref "U4") (pin "4") (pinfunction "IN_4") (pintype "passive"))
      (node (ref "U7") (pin "4") (pinfunction "IN_4") (pintype "passive"))
    )
    (net (code "30") (name "VDD") (class "Default")
      (node (ref "C10") (pin "2") (pinfunction "2_2") (pintype "passive"))
      (node (ref "C12") (pin "2") (pinfunction "2_2") (pintype "passive"))
      (node (ref "C14") (pin "2") (pinfunction "2_2") (pintype "passive"))
      (node (ref "R12") (pin "2") (pinfunction "2_2") (pintype "passive"))
      (node (ref "R4") (pin "2") (pinfunction "2_2") (pintype "passive"))
      (node (ref "R5") (pin "2") (pinfunction "2_2") (pintype "passive"))
      (node (ref "U2") (pin "11") (pinfunction "VDD3P3_RTC_11") (pintype "passive"))
      (node (ref "U2") (pin "17") (pinfunction "VDD3P3_CPU_17") (pintype "passive"))
      (node (ref "U2") (pin "2") (pinfunction "VDD3P3_2") (pintype "passive"))
      (node (ref "U2") (pin "3") (pinfunction "VDD3P3_3") (pintype "passive"))
      (node (ref "U2") (pin "31") (pinfunction "VDDA_31") (pintype "passive"))
      (node (ref "U2") (pin "32") (pinfunction "VDDA_32") (pintype "passive"))
      (node (ref "U7") (pin "1") (pinfunction "OUT_1") (pintype "passive"))
    )
    (net (code "31") (name "unconnected-(U1-INT#-Pad13)") (class "Default")
      (node (ref "U1") (pin "13") (pinfunction "INT#_13") (pintype "passive+no_connect"))
    )
    (net (code "32") (name "unconnected-(U1-NC-Pad1)") (class "Default")
      (node (ref "U1") (pin "1") (pinfunction "NC_1") (pintype "passive+no_connect"))
    )
    (net (code "33") (name "unconnected-(U1-NC-Pad5)") (class "Default")
      (node (ref "U1") (pin "5") (pinfunction "NC_5") (pintype "passive+no_connect"))
    )
    (net (code "34") (name "unconnected-(U1-NC-Pad6)") (class "Default")
      (node (ref "U1") (pin "6") (pinfunction "NC_6") (pintype "passive+no_connect"))
    )
    (net (code "35") (name "unconnected-(U1-NC-Pad7)") (class "Default")
      (node (ref "U1") (pin "7") (pinfunction "NC_7") (pintype "passive+no_connect"))
    )
    (net (code "36") (name "unconnected-(U1-NC-Pad8)") (class "Default")
      (node (ref "U1") (pin "8") (pinfunction "NC_8") (pintype "passive+no_connect"))
    )
    (net (code "37") (name "unconnected-(U1-NC-Pad14)") (class "Default")
      (node (ref "U1") (pin "14") (pinfunction "NC_14") (pintype "passive+no_connect"))
    )
    (net (code "38") (name "unconnected-(U2-SPICLK-Pad22)") (class "Default")
      (node (ref "U2") (pin "22") (pinfunction "SPICLK_22") (pintype "passive+no_connect"))
    )
    (net (code "39") (name "unconnected-(U2-SPICS0-Pad21)") (class "Default")
      (node (ref "U2") (pin "21") (pinfunction "SPICS0_21") (pintype "passive+no_connect"))
    )
    (net (code "40") (name "unconnected-(U2-SPID-Pad23)") (class "Default")
      (node (ref "U2") (pin "23") (pinfunction "SPID_23") (pintype "passive+no_connect"))
    )
    (net (code "41") (name "unconnected-(U2-SPIHD-Pad19)") (class "Default")
      (node (ref "U2") (pin "19") (pinfunction "SPIHD_19") (pintype "passive+no_connect"))
    )
    (net (code "42") (name "unconnected-(U2-SPIQ-Pad24)") (class "Default")
      (node (ref "U2") (pin "24") (pinfunction "SPIQ_24") (pintype "passive+no_connect"))
    )
    (net (code "43") (name "unconnected-(U2-SPIWP-Pad20)") (class "Default")
      (node (ref "U2") (pin "20") (pinfunction "SPIWP_20") (pintype "passive+no_connect"))
    )
    (net (code "44") (name "unconnected-(U2-U0RXD-Pad27)") (class "Default")
      (node (ref "U2") (pin "27") (pinfunction "U0RXD_27") (pintype "passive+no_connect"))
    )
    (net (code "45") (name "unconnected-(U2-U0TXD-Pad28)") (class "Default")
      (node (ref "U2") (pin "28") (pinfunction "U0TXD_28") (pintype "passive+no_connect"))
    )
    (net (code "46") (name "unconnected-(U5-Pad2)") (class "Default")
      (node (ref "U5") (pin "2") (pinfunction "2_2") (pintype "passive+no_connect"))
    )
  )
)
